# action_module.net
KiCad netlist of a schematic drawn in EAGLE
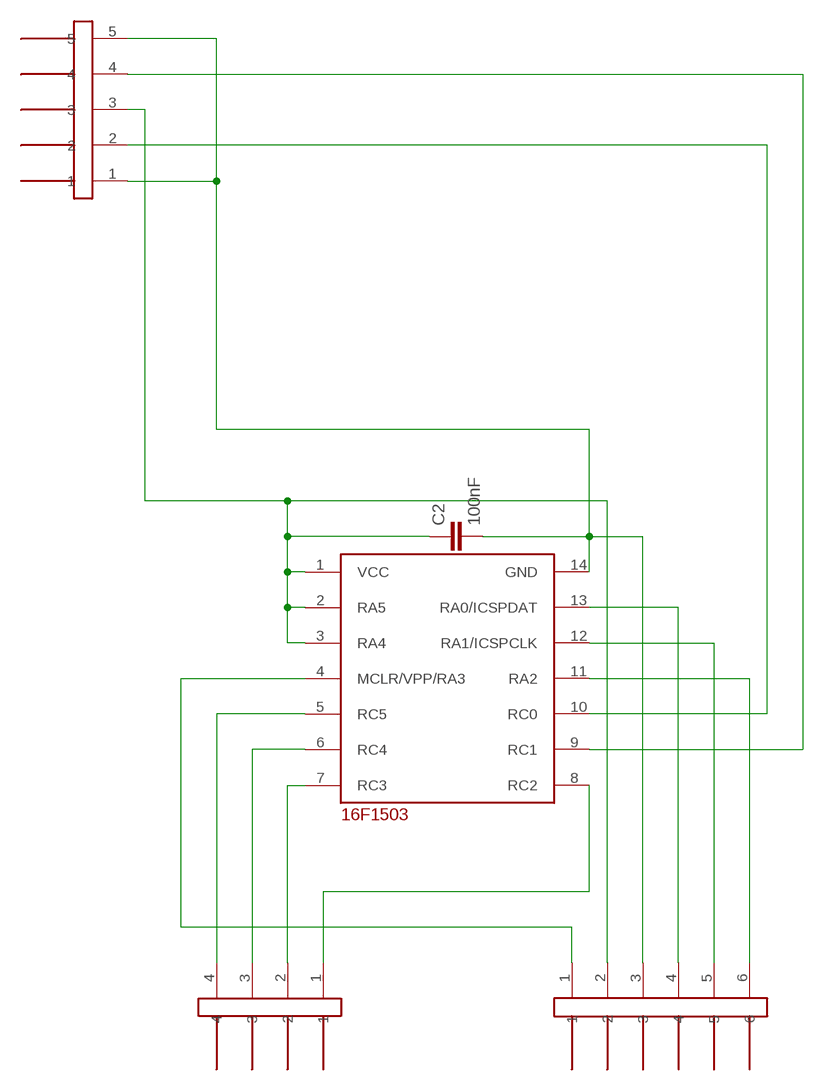
[diagram p0: schematic, sheet 1]

(export (version "E")
  (design (tool "Eeschema 10.0.6"))
  (components
    (comp (ref "C2")
      (value "100nF")
      (footprint "eagle-import:C0603")
      (libsource (lib "eagle-import") (part "C-EUC0603"))
    )
    (comp (ref "U$1")
      (value "16F103-TSSOP")
      (footprint "eagle-import:TSSOP14")
      (libsource (lib "eagle-import") (part "16F103-TSSOP"))
    )
    (comp (ref "U$4")
      (value "JUMPER5M-90")
      (footprint "eagle-import:JUMPER5M-90")
      (libsource (lib "eagle-import") (part "JUMPER5M-90"))
    )
    (comp (ref "U$8")
      (value "JUMPER6M")
      (footprint "eagle-import:JUMPER6M")
      (libsource (lib "eagle-import") (part "JUMPER6M"))
    )
    (comp (ref "U$9")
      (value "JUMPER4M")
      (footprint "eagle-import:JUMPER4M")
      (libsource (lib "eagle-import") (part "JUMPER4M"))
    )
  )
  (nets
    (net (code "1") (name "Net-(U$1-GND)") (class "Default")
      (node (ref "C2") (pin "2") (pinfunction "2_2") (pintype "passive"))
      (node (ref "U$1") (pin "14") (pinfunction "GND_14") (pintype "power_in"))
      (node (ref "U$4") (pin "1") (pinfunction "1_1") (pintype "bidirectional"))
      (node (ref "U$4") (pin "5") (pinfunction "5_5") (pintype "bidirectional"))
      (node (ref "U$8") (pin "3") (pinfunction "3_3") (pintype "bidirectional"))
    )
    (net (code "2") (name "Net-(U$1-MCLR{slash}VPP{slash}RA3)") (class "Default")
      (node (ref "U$1") (pin "4") (pinfunction "MCLR/VPP/RA3_4") (pintype "bidirectional"))
      (node (ref "U$8") (pin "1") (pinfunction "1_1") (pintype "bidirectional"))
    )
    (net (code "3") (name "Net-(U$1-RA0{slash}ICSPDAT)") (class "Default")
      (node (ref "U$1") (pin "13") (pinfunction "RA0/ICSPDAT_13") (pintype "bidirectional"))
      (node (ref "U$8") (pin "4") (pinfunction "4_4") (pintype "bidirectional"))
    )
    (net (code "4") (name "Net-(U$1-RA1{slash}ICSPCLK)") (class "Default")
      (node (ref "U$1") (pin "12") (pinfunction "RA1/ICSPCLK_12") (pintype "bidirectional"))
      (node (ref "U$8") (pin "5") (pinfunction "5_5") (pintype "bidirectional"))
    )
    (net (code "5") (name "Net-(U$1-RA2)") (class "Default")
      (node (ref "U$1") (pin "11") (pinfunction "RA2_11") (pintype "bidirectional"))
      (node (ref "U$8") (pin "6") (pinfunction "6_6") (pintype "bidirectional"))
    )
    (net (code "6") (name "Net-(U$1-RA4)") (class "Default")
      (node (ref "C2") (pin "1") (pinfunction "1_1") (pintype "passive"))
      (node (ref "U$1") (pin "1") (pinfunction "VCC_1") (pintype "power_in"))
      (node (ref "U$1") (pin "2") (pinfunction "RA5_2") (pintype "bidirectional"))
      (node (ref "U$1") (pin "3") (pinfunction "RA4_3") (pintype "bidirectional"))
      (node (ref "U$4") (pin "3") (pinfunction "3_3") (pintype "bidirectional"))
      (node (ref "U$8") (pin "2") (pinfunction "2_2") (pintype "bidirectional"))
    )
    (net (code "7") (name "Net-(U$1-RC0)") (class "Default")
      (node (ref "U$1") (pin "10") (pinfunction "RC0_10") (pintype "bidirectional"))
      (node (ref "U$4") (pin "2") (pinfunction "2_2") (pintype "bidirectional"))
    )
    (net (code "8") (name "Net-(U$1-RC1)") (class "Default")
      (node (ref "U$1") (pin "9") (pinfunction "RC1_9") (pintype "bidirectional"))
      (node (ref "U$4") (pin "4") (pinfunction "4_4") (pintype "bidirectional"))
    )
    (net (code "9") (name "Net-(U$1-RC2)") (class "Default")
      (node (ref "U$1") (pin "8") (pinfunction "RC2_8") (pintype "bidirectional"))
      (node (ref "U$9") (pin "1") (pinfunction "1_1") (pintype "bidirectional"))
    )
    (net (code "10") (name "Net-(U$1-RC3)") (class "Default")
      (node (ref "U$1") (pin "7") (pinfunction "RC3_7") (pintype "bidirectional"))
      (node (ref "U$9") (pin "2") (pinfunction "2_2") (pintype "bidirectional"))
    )
    (net (code "11") (name "Net-(U$1-RC4)") (class "Default")
      (node (ref "U$1") (pin "6") (pinfunction "RC4_6") (pintype "bidirectional"))
      (node (ref "U$9") (pin "3") (pinfunction "3_3") (pintype "bidirectional"))
    )
    (net (code "12") (name "Net-(U$1-RC5)") (class "Default")
      (node (ref "U$1") (pin "5") (pinfunction "RC5_5") (pintype "bidirectional"))
      (node (ref "U$9") (pin "4") (pinfunction "4_4") (pintype "bidirectional"))
    )
  )
)
